# Sheet_Power.net
KiCad netlist of a schematic drawn in Altium Designer
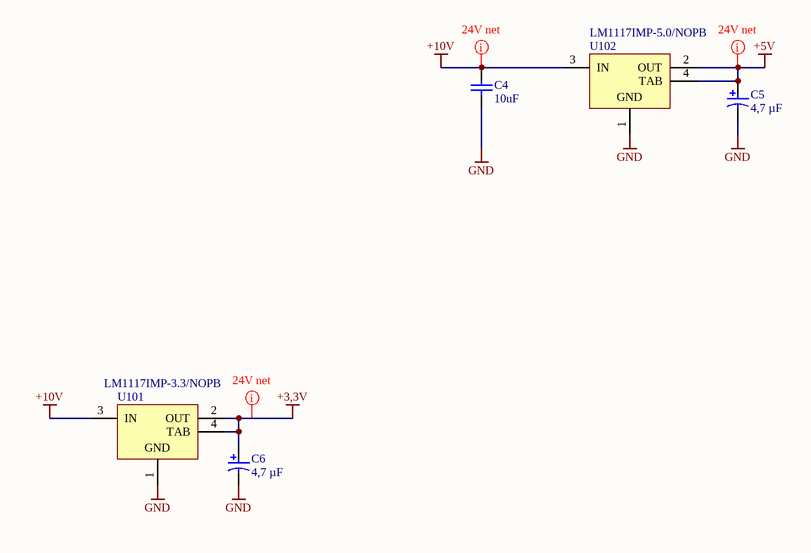
[diagram p0: Sheet_Power.SchDoc]

(export (version "E")
  (design (tool "Eeschema 10.0.6"))
  (components
    (comp (ref "C4")
      (value "10uF")
      (footprint "CAPC1206(3216)190_N")
      (description "CAP 10uF 25V -20% to +80% 1206 (3216 Metric) Thickness 1.9mm SMD")
      (fields
        (field (name "TOLERANCE") "-20% to +80%")
        (field (name "MANUFACTURER") "Wurth Electronics Inc.")
      )
      (libsource (lib "Altium Vault EMBL 3") (part "CMP-00471-2"))
    )
    (comp (ref "C5")
      (value "4,7 µF")
      (footprint "A Package")
      (description "4,7 µF; 6V; Gr. A; T491A475K006AT")
      (fields (field (name "MANUFACTURER") "KEMET") (field (name "TOLERANCE") "±10%"))
      (libsource (lib "Altium Vault EMBL 3") (part "CMP-001-0039-3"))
    )
    (comp (ref "C6")
      (value "4,7 µF")
      (footprint "A Package")
      (description "4,7 µF; 6V; Gr. A; T491A475K006AT")
      (fields (field (name "MANUFACTURER") "KEMET") (field (name "TOLERANCE") "±10%"))
      (libsource (lib "Altium Vault EMBL 3") (part "CMP-001-0039-3"))
    )
    (comp (ref "U101")
      (value "LM1117IMP-3.3/NOPB")
      (footprint "DCY0004A_N")
      (description "800mA Low-Dropout Linear Regulator, 4-pin SOT-223, Pb-Free")
      (fields (field (name "MANUFACTURER") "Texas Instruments"))
      (libsource (lib "Altium Vault EMBL") (part "CMP-00484-1"))
    )
    (comp (ref "U102")
      (value "LM1117IMP-5.0/NOPB")
      (footprint "DCY0004A_M")
      (description "800mA Low-Dropout Linear Regulator, 4-pin SOT-223, Pb-Free")
      (fields (field (name "MANUFACTURER") "Texas Instruments"))
      (libsource (lib "Altium Vault EMBL") (part "CMP-00485-1"))
    )
  )
  (nets
    (net (code "1") (name "+3,3V") (class "Default")
      (node (ref "C6") (pin "1") (pinfunction "1_1") (pintype "passive"))
      (node (ref "U101") (pin "2") (pinfunction "OUT_2") (pintype "power_in"))
      (node (ref "U101") (pin "4") (pinfunction "TAB_4") (pintype "power_in"))
    )
    (net (code "2") (name "+5V") (class "Default")
      (node (ref "C5") (pin "1") (pinfunction "1_1") (pintype "passive"))
      (node (ref "U102") (pin "2") (pinfunction "OUT_2") (pintype "power_in"))
      (node (ref "U102") (pin "4") (pinfunction "TAB_4") (pintype "power_in"))
    )
    (net (code "3") (name "+10V") (class "Default")
      (node (ref "C4") (pin "2") (pinfunction "2_2") (pintype "passive"))
      (node (ref "U101") (pin "3") (pinfunction "IN_3") (pintype "power_in"))
      (node (ref "U102") (pin "3") (pinfunction "IN_3") (pintype "power_in"))
    )
    (net (code "4") (name "GND") (class "Default")
      (node (ref "C4") (pin "1") (pinfunction "1_1") (pintype "passive"))
      (node (ref "C5") (pin "2") (pinfunction "2_2") (pintype "passive"))
      (node (ref "C6") (pin "2") (pinfunction "2_2") (pintype "passive"))
      (node (ref "U101") (pin "1") (pinfunction "GND_1") (pintype "power_in"))
      (node (ref "U102") (pin "1") (pinfunction "GND_1") (pintype "power_in"))
    )
  )
)
